# inputsheild_3.net
KiCad netlist of a schematic drawn in EAGLE
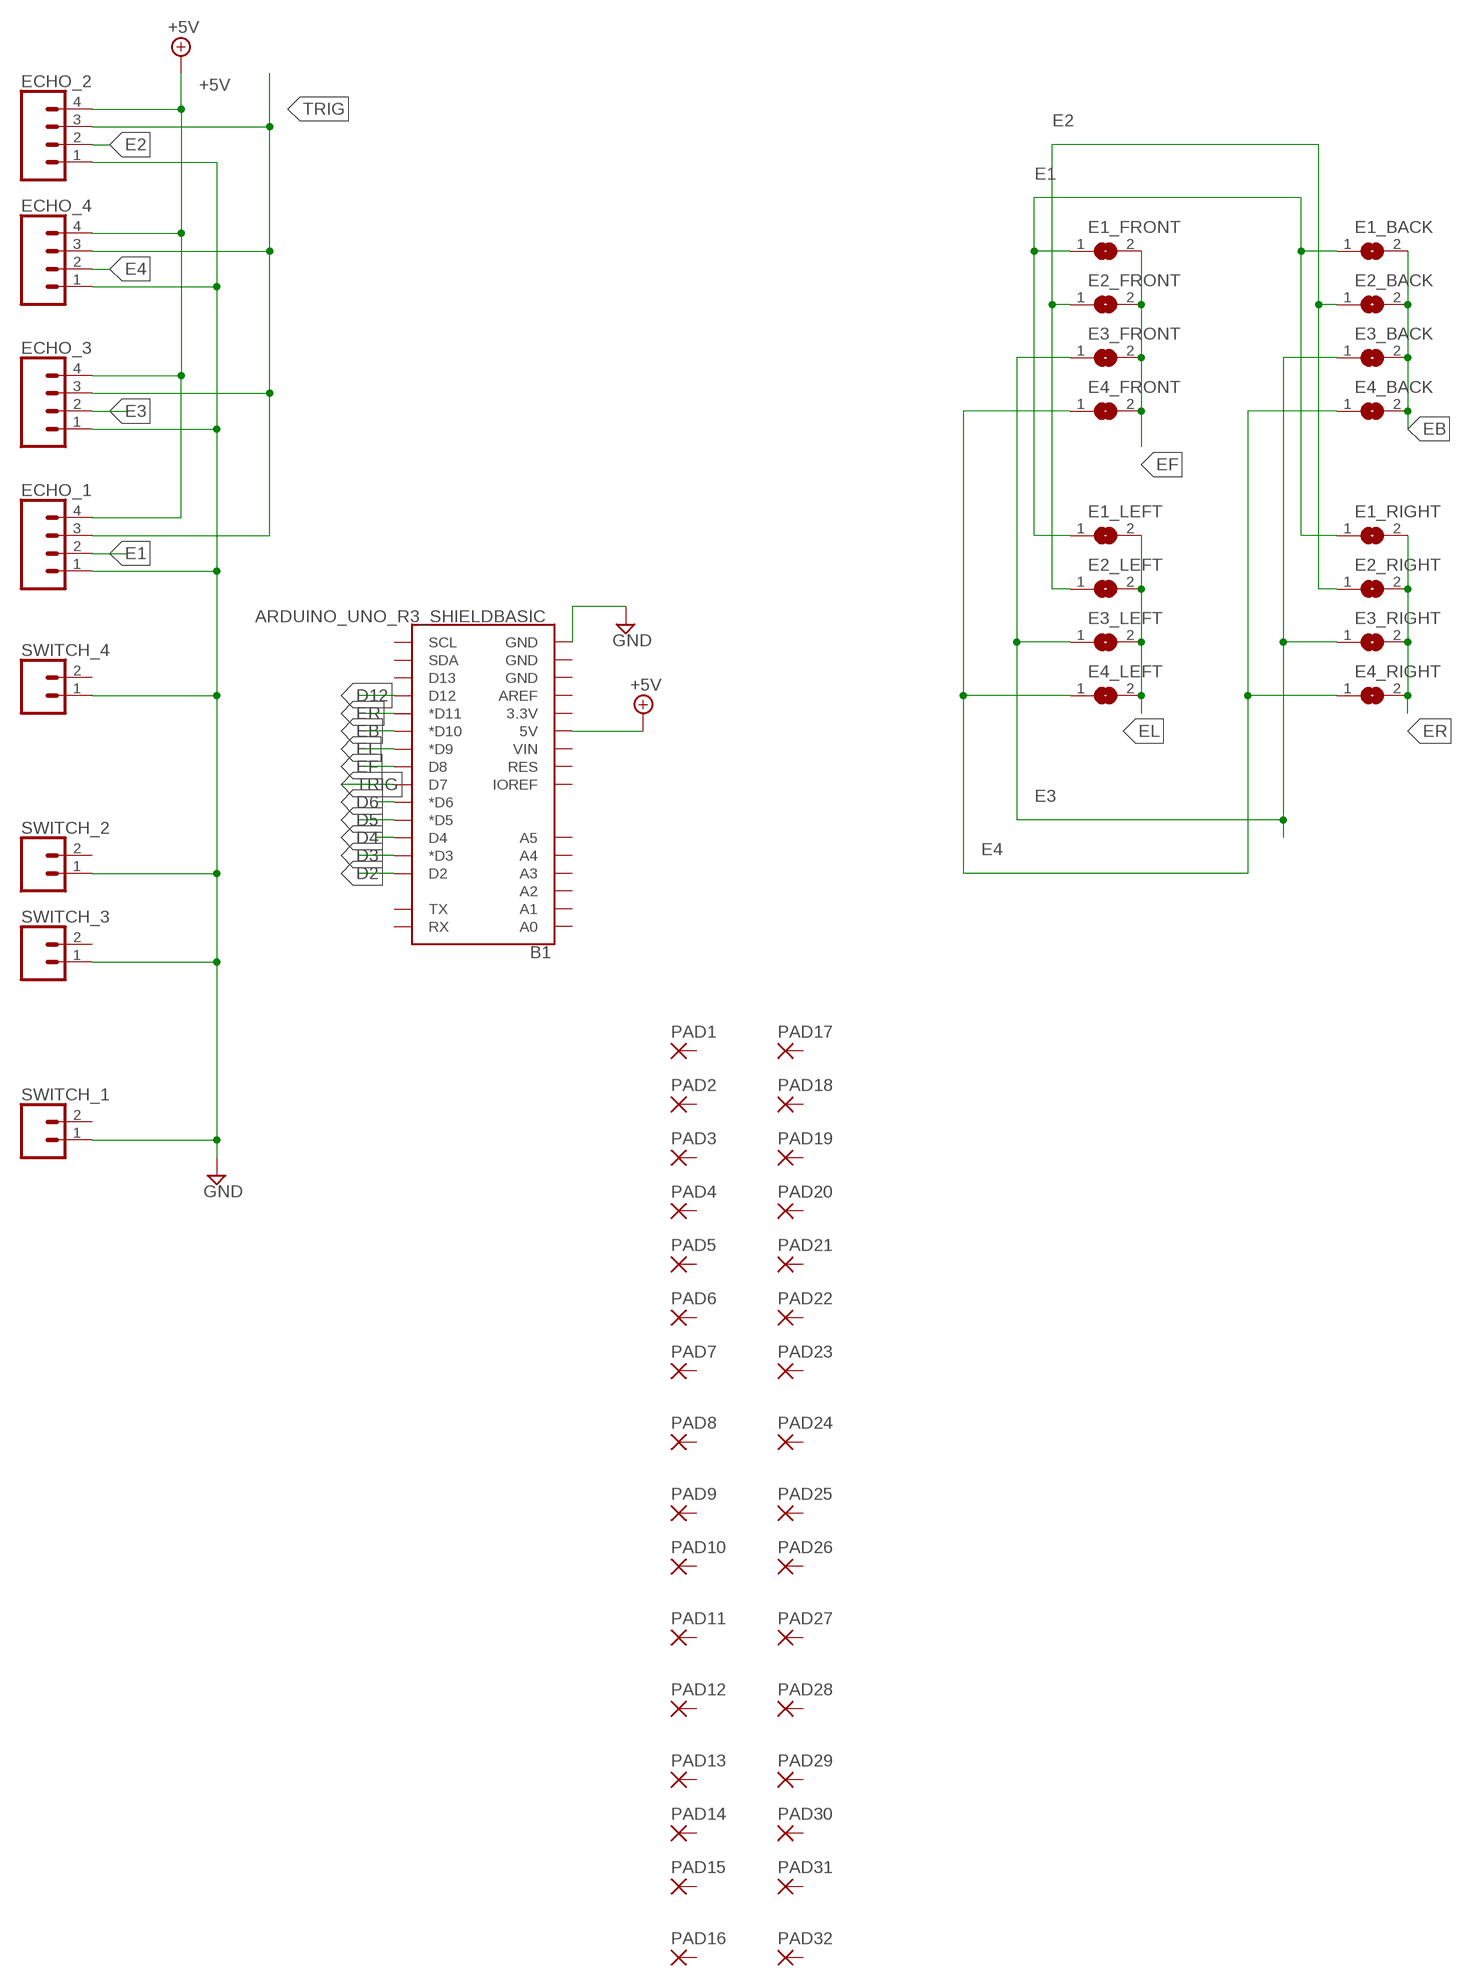
[diagram p0: schematic, sheet 1]

(export (version "E")
  (design (tool "Eeschema 10.0.6"))
  (components
    (comp (ref "B1")
      (value "ARDUINO_UNO_R3_SHIELDBASIC")
      (footprint "eagle-import:UNO_R3_SHIELD")
      (libsource (lib "eagle-import") (part "ARDUINO_UNO_R3_SHIELDBASIC"))
    )
    (comp (ref "E1_BACK")
      (value "SJ")
      (footprint "eagle-import:SJ")
      (libsource (lib "eagle-import") (part "SJ"))
    )
    (comp (ref "E1_FRONT")
      (value "SJ")
      (footprint "eagle-import:SJ")
      (libsource (lib "eagle-import") (part "SJ"))
    )
    (comp (ref "E1_LEFT")
      (value "SJ")
      (footprint "eagle-import:SJ")
      (libsource (lib "eagle-import") (part "SJ"))
    )
    (comp (ref "E1_RIGHT")
      (value "SJ")
      (footprint "eagle-import:SJ")
      (libsource (lib "eagle-import") (part "SJ"))
    )
    (comp (ref "E2_BACK")
      (value "SJ")
      (footprint "eagle-import:SJ")
      (libsource (lib "eagle-import") (part "SJ"))
    )
    (comp (ref "E2_FRONT")
      (value "SJ")
      (footprint "eagle-import:SJ")
      (libsource (lib "eagle-import") (part "SJ"))
    )
    (comp (ref "E2_LEFT")
      (value "SJ")
      (footprint "eagle-import:SJ")
      (libsource (lib "eagle-import") (part "SJ"))
    )
    (comp (ref "E2_RIGHT")
      (value "SJ")
      (footprint "eagle-import:SJ")
      (libsource (lib "eagle-import") (part "SJ"))
    )
    (comp (ref "E3_BACK")
      (value "SJ")
      (footprint "eagle-import:SJ")
      (libsource (lib "eagle-import") (part "SJ"))
    )
    (comp (ref "E3_FRONT")
      (value "SJ")
      (footprint "eagle-import:SJ")
      (libsource (lib "eagle-import") (part "SJ"))
    )
    (comp (ref "E3_LEFT")
      (value "SJ")
      (footprint "eagle-import:SJ")
      (libsource (lib "eagle-import") (part "SJ"))
    )
    (comp (ref "E3_RIGHT")
      (value "SJ")
      (footprint "eagle-import:SJ")
      (libsource (lib "eagle-import") (part "SJ"))
    )
    (comp (ref "E4_BACK")
      (value "SJ")
      (footprint "eagle-import:SJ")
      (libsource (lib "eagle-import") (part "SJ"))
    )
    (comp (ref "E4_FRONT")
      (value "SJ")
      (footprint "eagle-import:SJ")
      (libsource (lib "eagle-import") (part "SJ"))
    )
    (comp (ref "E4_LEFT")
      (value "SJ")
      (footprint "eagle-import:SJ")
      (libsource (lib "eagle-import") (part "SJ"))
    )
    (comp (ref "E4_RIGHT")
      (value "SJ")
      (footprint "eagle-import:SJ")
      (libsource (lib "eagle-import") (part "SJ"))
    )
    (comp (ref "ECHO_1")
      (value "CONN_04SCREW")
      (footprint "eagle-import:SCREWTERMINAL-3.5MM-4")
      (libsource (lib "eagle-import") (part "CONN_04SCREW"))
    )
    (comp (ref "ECHO_2")
      (value "CONN_04SCREW")
      (footprint "eagle-import:SCREWTERMINAL-3.5MM-4")
      (libsource (lib "eagle-import") (part "CONN_04SCREW"))
    )
    (comp (ref "ECHO_3")
      (value "CONN_04SCREW")
      (footprint "eagle-import:SCREWTERMINAL-3.5MM-4")
      (libsource (lib "eagle-import") (part "CONN_04SCREW"))
    )
    (comp (ref "ECHO_4")
      (value "CONN_04SCREW")
      (footprint "eagle-import:SCREWTERMINAL-3.5MM-4")
      (libsource (lib "eagle-import") (part "CONN_04SCREW"))
    )
    (comp (ref "PAD1")
      (value "SMD5")
      (footprint "eagle-import:SMD2,54-5,08")
      (libsource (lib "eagle-import") (part "SMD5"))
    )
    (comp (ref "PAD2")
      (value "SMD5")
      (footprint "eagle-import:SMD2,54-5,08")
      (libsource (lib "eagle-import") (part "SMD5"))
    )
    (comp (ref "PAD3")
      (value "SMD5")
      (footprint "eagle-import:SMD2,54-5,08")
      (libsource (lib "eagle-import") (part "SMD5"))
    )
    (comp (ref "PAD4")
      (value "SMD5")
      (footprint "eagle-import:SMD2,54-5,08")
      (libsource (lib "eagle-import") (part "SMD5"))
    )
    (comp (ref "PAD5")
      (value "SMD5")
      (footprint "eagle-import:SMD2,54-5,08")
      (libsource (lib "eagle-import") (part "SMD5"))
    )
    (comp (ref "PAD6")
      (value "SMD5")
      (footprint "eagle-import:SMD2,54-5,08")
      (libsource (lib "eagle-import") (part "SMD5"))
    )
    (comp (ref "PAD7")
      (value "SMD5")
      (footprint "eagle-import:SMD2,54-5,08")
      (libsource (lib "eagle-import") (part "SMD5"))
    )
    (comp (ref "PAD8")
      (value "SMD5")
      (footprint "eagle-import:SMD2,54-5,08")
      (libsource (lib "eagle-import") (part "SMD5"))
    )
    (comp (ref "PAD9")
      (value "SMD5")
      (footprint "eagle-import:SMD2,54-5,08")
      (libsource (lib "eagle-import") (part "SMD5"))
    )
    (comp (ref "PAD10")
      (value "SMD5")
      (footprint "eagle-import:SMD2,54-5,08")
      (libsource (lib "eagle-import") (part "SMD5"))
    )
    (comp (ref "PAD11")
      (value "SMD5")
      (footprint "eagle-import:SMD2,54-5,08")
      (libsource (lib "eagle-import") (part "SMD5"))
    )
    (comp (ref "PAD12")
      (value "SMD5")
      (footprint "eagle-import:SMD2,54-5,08")
      (libsource (lib "eagle-import") (part "SMD5"))
    )
    (comp (ref "PAD13")
      (value "SMD5")
      (footprint "eagle-import:SMD2,54-5,08")
      (libsource (lib "eagle-import") (part "SMD5"))
    )
    (comp (ref "PAD14")
      (value "SMD5")
      (footprint "eagle-import:SMD2,54-5,08")
      (libsource (lib "eagle-import") (part "SMD5"))
    )
    (comp (ref "PAD15")
      (value "SMD5")
      (footprint "eagle-import:SMD2,54-5,08")
      (libsource (lib "eagle-import") (part "SMD5"))
    )
    (comp (ref "PAD16")
      (value "SMD5")
      (footprint "eagle-import:SMD2,54-5,08")
      (libsource (lib "eagle-import") (part "SMD5"))
    )
    (comp (ref "PAD17")
      (value "SMD5")
      (footprint "eagle-import:SMD2,54-5,08")
      (libsource (lib "eagle-import") (part "SMD5"))
    )
    (comp (ref "PAD18")
      (value "SMD5")
      (footprint "eagle-import:SMD2,54-5,08")
      (libsource (lib "eagle-import") (part "SMD5"))
    )
    (comp (ref "PAD19")
      (value "SMD5")
      (footprint "eagle-import:SMD2,54-5,08")
      (libsource (lib "eagle-import") (part "SMD5"))
    )
    (comp (ref "PAD20")
      (value "SMD5")
      (footprint "eagle-import:SMD2,54-5,08")
      (libsource (lib "eagle-import") (part "SMD5"))
    )
    (comp (ref "PAD21")
      (value "SMD5")
      (footprint "eagle-import:SMD2,54-5,08")
      (libsource (lib "eagle-import") (part "SMD5"))
    )
    (comp (ref "PAD22")
      (value "SMD5")
      (footprint "eagle-import:SMD2,54-5,08")
      (libsource (lib "eagle-import") (part "SMD5"))
    )
    (comp (ref "PAD23")
      (value "SMD5")
      (footprint "eagle-import:SMD2,54-5,08")
      (libsource (lib "eagle-import") (part "SMD5"))
    )
    (comp (ref "PAD24")
      (value "SMD5")
      (footprint "eagle-import:SMD2,54-5,08")
      (libsource (lib "eagle-import") (part "SMD5"))
    )
    (comp (ref "PAD25")
      (value "SMD5")
      (footprint "eagle-import:SMD2,54-5,08")
      (libsource (lib "eagle-import") (part "SMD5"))
    )
    (comp (ref "PAD26")
      (value "SMD5")
      (footprint "eagle-import:SMD2,54-5,08")
      (libsource (lib "eagle-import") (part "SMD5"))
    )
    (comp (ref "PAD27")
      (value "SMD5")
      (footprint "eagle-import:SMD2,54-5,08")
      (libsource (lib "eagle-import") (part "SMD5"))
    )
    (comp (ref "PAD28")
      (value "SMD5")
      (footprint "eagle-import:SMD2,54-5,08")
      (libsource (lib "eagle-import") (part "SMD5"))
    )
    (comp (ref "PAD29")
      (value "SMD5")
      (footprint "eagle-import:SMD2,54-5,08")
      (libsource (lib "eagle-import") (part "SMD5"))
    )
    (comp (ref "PAD30")
      (value "SMD5")
      (footprint "eagle-import:SMD2,54-5,08")
      (libsource (lib "eagle-import") (part "SMD5"))
    )
    (comp (ref "PAD31")
      (value "SMD5")
      (footprint "eagle-import:SMD2,54-5,08")
      (libsource (lib "eagle-import") (part "SMD5"))
    )
    (comp (ref "PAD32")
      (value "SMD5")
      (footprint "eagle-import:SMD2,54-5,08")
      (libsource (lib "eagle-import") (part "SMD5"))
    )
    (comp (ref "SWITCH_1")
      (value "CONN_023.5MM")
      (footprint "eagle-import:SCREWTERMINAL-3.5MM-2")
      (libsource (lib "eagle-import") (part "CONN_023.5MM"))
    )
    (comp (ref "SWITCH_2")
      (value "CONN_023.5MM")
      (footprint "eagle-import:SCREWTERMINAL-3.5MM-2")
      (libsource (lib "eagle-import") (part "CONN_023.5MM"))
    )
    (comp (ref "SWITCH_3")
      (value "CONN_023.5MM")
      (footprint "eagle-import:SCREWTERMINAL-3.5MM-2")
      (libsource (lib "eagle-import") (part "CONN_023.5MM"))
    )
    (comp (ref "SWITCH_4")
      (value "CONN_023.5MM")
      (footprint "eagle-import:SCREWTERMINAL-3.5MM-2")
      (libsource (lib "eagle-import") (part "CONN_023.5MM"))
    )
  )
  (nets
    (net (code "1") (name "+5V") (class "Default")
      (node (ref "B1") (pin "5V") (pinfunction "5V_5V") (pintype "bidirectional"))
      (node (ref "ECHO_1") (pin "4") (pinfunction "4_4") (pintype "passive"))
      (node (ref "ECHO_2") (pin "4") (pinfunction "4_4") (pintype "passive"))
      (node (ref "ECHO_3") (pin "4") (pinfunction "4_4") (pintype "passive"))
      (node (ref "ECHO_4") (pin "4") (pinfunction "4_4") (pintype "passive"))
    )
    (net (code "2") (name "D2") (class "Default")
      (node (ref "B1") (pin "D2") (pinfunction "D2_D2") (pintype "bidirectional"))
    )
    (net (code "3") (name "D3") (class "Default")
      (node (ref "B1") (pin "D3") (pinfunction "*D3_D3") (pintype "bidirectional"))
    )
    (net (code "4") (name "D4") (class "Default")
      (node (ref "B1") (pin "D4") (pinfunction "D4_D4") (pintype "bidirectional"))
    )
    (net (code "5") (name "D5") (class "Default")
      (node (ref "B1") (pin "D5") (pinfunction "*D5_D5") (pintype "bidirectional"))
    )
    (net (code "6") (name "D6") (class "Default")
      (node (ref "B1") (pin "D6") (pinfunction "*D6_D6") (pintype "bidirectional"))
    )
    (net (code "7") (name "D12") (class "Default")
      (node (ref "B1") (pin "D12") (pinfunction "D12_D12") (pintype "bidirectional"))
    )
    (net (code "8") (name "E1") (class "Default")
      (node (ref "E1_BACK") (pin "1") (pinfunction "1_1") (pintype "passive"))
      (node (ref "E1_FRONT") (pin "1") (pinfunction "1_1") (pintype "passive"))
      (node (ref "E1_LEFT") (pin "1") (pinfunction "1_1") (pintype "passive"))
      (node (ref "E1_RIGHT") (pin "1") (pinfunction "1_1") (pintype "passive"))
      (node (ref "ECHO_1") (pin "2") (pinfunction "2_2") (pintype "passive"))
    )
    (net (code "9") (name "E2") (class "Default")
      (node (ref "E2_BACK") (pin "1") (pinfunction "1_1") (pintype "passive"))
      (node (ref "E2_FRONT") (pin "1") (pinfunction "1_1") (pintype "passive"))
      (node (ref "E2_LEFT") (pin "1") (pinfunction "1_1") (pintype "passive"))
      (node (ref "E2_RIGHT") (pin "1") (pinfunction "1_1") (pintype "passive"))
      (node (ref "ECHO_2") (pin "2") (pinfunction "2_2") (pintype "passive"))
    )
    (net (code "10") (name "E3") (class "Default")
      (node (ref "E3_BACK") (pin "1") (pinfunction "1_1") (pintype "passive"))
      (node (ref "E3_FRONT") (pin "1") (pinfunction "1_1") (pintype "passive"))
      (node (ref "E3_LEFT") (pin "1") (pinfunction "1_1") (pintype "passive"))
      (node (ref "E3_RIGHT") (pin "1") (pinfunction "1_1") (pintype "passive"))
      (node (ref "ECHO_3") (pin "2") (pinfunction "2_2") (pintype "passive"))
    )
    (net (code "11") (name "E4") (class "Default")
      (node (ref "E4_BACK") (pin "1") (pinfunction "1_1") (pintype "passive"))
      (node (ref "E4_FRONT") (pin "1") (pinfunction "1_1") (pintype "passive"))
      (node (ref "E4_LEFT") (pin "1") (pinfunction "1_1") (pintype "passive"))
      (node (ref "E4_RIGHT") (pin "1") (pinfunction "1_1") (pintype "passive"))
      (node (ref "ECHO_4") (pin "2") (pinfunction "2_2") (pintype "passive"))
    )
    (net (code "12") (name "EB") (class "Default")
      (node (ref "B1") (pin "D10") (pinfunction "*D10_D10") (pintype "bidirectional"))
      (node (ref "E1_BACK") (pin "2") (pinfunction "2_2") (pintype "passive"))
      (node (ref "E2_BACK") (pin "2") (pinfunction "2_2") (pintype "passive"))
      (node (ref "E3_BACK") (pin "2") (pinfunction "2_2") (pintype "passive"))
      (node (ref "E4_BACK") (pin "2") (pinfunction "2_2") (pintype "passive"))
    )
    (net (code "13") (name "EF") (class "Default")
      (node (ref "B1") (pin "D8") (pinfunction "D8_D8") (pintype "bidirectional"))
      (node (ref "E1_FRONT") (pin "2") (pinfunction "2_2") (pintype "passive"))
      (node (ref "E2_FRONT") (pin "2") (pinfunction "2_2") (pintype "passive"))
      (node (ref "E3_FRONT") (pin "2") (pinfunction "2_2") (pintype "passive"))
      (node (ref "E4_FRONT") (pin "2") (pinfunction "2_2") (pintype "passive"))
    )
    (net (code "14") (name "EL") (class "Default")
      (node (ref "B1") (pin "D9") (pinfunction "*D9_D9") (pintype "bidirectional"))
      (node (ref "E1_LEFT") (pin "2") (pinfunction "2_2") (pintype "passive"))
      (node (ref "E2_LEFT") (pin "2") (pinfunction "2_2") (pintype "passive"))
      (node (ref "E3_LEFT") (pin "2") (pinfunction "2_2") (pintype "passive"))
      (node (ref "E4_LEFT") (pin "2") (pinfunction "2_2") (pintype "passive"))
    )
    (net (code "15") (name "ER") (class "Default")
      (node (ref "B1") (pin "D11") (pinfunction "*D11_D11") (pintype "bidirectional"))
      (node (ref "E1_RIGHT") (pin "2") (pinfunction "2_2") (pintype "passive"))
      (node (ref "E2_RIGHT") (pin "2") (pinfunction "2_2") (pintype "passive"))
      (node (ref "E3_RIGHT") (pin "2") (pinfunction "2_2") (pintype "passive"))
      (node (ref "E4_RIGHT") (pin "2") (pinfunction "2_2") (pintype "passive"))
    )
    (net (code "16") (name "GND") (class "Default")
      (node (ref "B1") (pin "GND@0") (pinfunction "GND_GND@0") (pintype "bidirectional"))
      (node (ref "ECHO_1") (pin "1") (pinfunction "1_1") (pintype "passive"))
      (node (ref "ECHO_2") (pin "1") (pinfunction "1_1") (pintype "passive"))
      (node (ref "ECHO_3") (pin "1") (pinfunction "1_1") (pintype "passive"))
      (node (ref "ECHO_4") (pin "1") (pinfunction "1_1") (pintype "passive"))
      (node (ref "SWITCH_1") (pin "1") (pinfunction "1_1") (pintype "passive"))
      (node (ref "SWITCH_2") (pin "1") (pinfunction "1_1") (pintype "passive"))
      (node (ref "SWITCH_3") (pin "1") (pinfunction "1_1") (pintype "passive"))
      (node (ref "SWITCH_4") (pin "1") (pinfunction "1_1") (pintype "passive"))
    )
    (net (code "17") (name "TRIG") (class "Default")
      (node (ref "B1") (pin "D7") (pinfunction "D7_D7") (pintype "bidirectional"))
      (node (ref "ECHO_1") (pin "3") (pinfunction "3_3") (pintype "passive"))
      (node (ref "ECHO_2") (pin "3") (pinfunction "3_3") (pintype "passive"))
      (node (ref "ECHO_3") (pin "3") (pinfunction "3_3") (pintype "passive"))
      (node (ref "ECHO_4") (pin "3") (pinfunction "3_3") (pintype "passive"))
    )
    (net (code "18") (name "unconnected-(B1-GND-PadGND@1)") (class "Default")
      (node (ref "B1") (pin "GND@1") (pinfunction "GND_GND@1") (pintype "bidirectional"))
    )
    (net (code "19") (name "unconnected-(B1-GND-PadGND@2)") (class "Default")
      (node (ref "B1") (pin "GND@2") (pinfunction "GND_GND@2") (pintype "bidirectional"))
    )
    (net (code "20") (name "unconnected-(B1-Pad3.3V)") (class "Default")
      (node (ref "B1") (pin "3.3V") (pinfunction "3.3V_3.3V") (pintype "bidirectional"))
    )
    (net (code "21") (name "unconnected-(B1-PadA0)") (class "Default")
      (node (ref "B1") (pin "A0") (pinfunction "A0_A0") (pintype "bidirectional"))
    )
    (net (code "22") (name "unconnected-(B1-PadA1)") (class "Default")
      (node (ref "B1") (pin "A1") (pinfunction "A1_A1") (pintype "bidirectional"))
    )
    (net (code "23") (name "unconnected-(B1-PadA2)") (class "Default")
      (node (ref "B1") (pin "A2") (pinfunction "A2_A2") (pintype "bidirectional"))
    )
    (net (code "24") (name "unconnected-(B1-PadA3)") (class "Default")
      (node (ref "B1") (pin "A3") (pinfunction "A3_A3") (pintype "bidirectional"))
    )
    (net (code "25") (name "unconnected-(B1-PadA4)") (class "Default")
      (node (ref "B1") (pin "A4") (pinfunction "A4_A4") (pintype "bidirectional"))
    )
    (net (code "26") (name "unconnected-(B1-PadA5)") (class "Default")
      (node (ref "B1") (pin "A5") (pinfunction "A5_A5") (pintype "bidirectional"))
    )
    (net (code "27") (name "unconnected-(B1-PadAREF)") (class "Default")
      (node (ref "B1") (pin "AREF") (pinfunction "AREF_AREF") (pintype "bidirectional"))
    )
    (net (code "28") (name "unconnected-(B1-PadD13)") (class "Default")
      (node (ref "B1") (pin "D13") (pinfunction "D13_D13") (pintype "bidirectional"))
    )
    (net (code "29") (name "unconnected-(B1-PadIOREF)") (class "Default")
      (node (ref "B1") (pin "IOREF") (pinfunction "IOREF_IOREF") (pintype "bidirectional"))
    )
    (net (code "30") (name "unconnected-(B1-PadRES)") (class "Default")
      (node (ref "B1") (pin "RES") (pinfunction "RES_RES") (pintype "bidirectional"))
    )
    (net (code "31") (name "unconnected-(B1-PadRX)") (class "Default")
      (node (ref "B1") (pin "RX") (pinfunction "RX_RX") (pintype "bidirectional"))
    )
    (net (code "32") (name "unconnected-(B1-PadSCL)") (class "Default")
      (node (ref "B1") (pin "SCL") (pinfunction "SCL_SCL") (pintype "bidirectional"))
    )
    (net (code "33") (name "unconnected-(B1-PadSDA)") (class "Default")
      (node (ref "B1") (pin "SDA") (pinfunction "SDA_SDA") (pintype "bidirectional"))
    )
    (net (code "34") (name "unconnected-(B1-PadTX)") (class "Default")
      (node (ref "B1") (pin "TX") (pinfunction "TX_TX") (pintype "bidirectional"))
    )
    (net (code "35") (name "unconnected-(B1-PadVIN)") (class "Default")
      (node (ref "B1") (pin "VIN") (pinfunction "VIN_VIN") (pintype "bidirectional"))
    )
    (net (code "36") (name "unconnected-(PAD1-P-Pad1)") (class "Default")
      (node (ref "PAD1") (pin "1") (pinfunction "P_1") (pintype "passive"))
    )
    (net (code "37") (name "unconnected-(PAD2-P-Pad1)") (class "Default")
      (node (ref "PAD2") (pin "1") (pinfunction "P_1") (pintype "passive"))
    )
    (net (code "38") (name "unconnected-(PAD3-P-Pad1)") (class "Default")
      (node (ref "PAD3") (pin "1") (pinfunction "P_1") (pintype "passive"))
    )
    (net (code "39") (name "unconnected-(PAD4-P-Pad1)") (class "Default")
      (node (ref "PAD4") (pin "1") (pinfunction "P_1") (pintype "passive"))
    )
    (net (code "40") (name "unconnected-(PAD5-P-Pad1)") (class "Default")
      (node (ref "PAD5") (pin "1") (pinfunction "P_1") (pintype "passive"))
    )
    (net (code "41") (name "unconnected-(PAD6-P-Pad1)") (class "Default")
      (node (ref "PAD6") (pin "1") (pinfunction "P_1") (pintype "passive"))
    )
    (net (code "42") (name "unconnected-(PAD7-P-Pad1)") (class "Default")
      (node (ref "PAD7") (pin "1") (pinfunction "P_1") (pintype "passive"))
    )
    (net (code "43") (name "unconnected-(PAD8-P-Pad1)") (class "Default")
      (node (ref "PAD8") (pin "1") (pinfunction "P_1") (pintype "passive"))
    )
    (net (code "44") (name "unconnected-(PAD9-P-Pad1)") (class "Default")
      (node (ref "PAD9") (pin "1") (pinfunction "P_1") (pintype "passive"))
    )
    (net (code "45") (name "unconnected-(PAD10-P-Pad1)") (class "Default")
      (node (ref "PAD10") (pin "1") (pinfunction "P_1") (pintype "passive"))
    )
    (net (code "46") (name "unconnected-(PAD11-P-Pad1)") (class "Default")
      (node (ref "PAD11") (pin "1") (pinfunction "P_1") (pintype "passive"))
    )
    (net (code "47") (name "unconnected-(PAD12-P-Pad1)") (class "Default")
      (node (ref "PAD12") (pin "1") (pinfunction "P_1") (pintype "passive"))
    )
    (net (code "48") (name "unconnected-(PAD13-P-Pad1)") (class "Default")
      (node (ref "PAD13") (pin "1") (pinfunction "P_1") (pintype "passive"))
    )
    (net (code "49") (name "unconnected-(PAD14-P-Pad1)") (class "Default")
      (node (ref "PAD14") (pin "1") (pinfunction "P_1") (pintype "passive"))
    )
    (net (code "50") (name "unconnected-(PAD15-P-Pad1)") (class "Default")
      (node (ref "PAD15") (pin "1") (pinfunction "P_1") (pintype "passive"))
    )
    (net (code "51") (name "unconnected-(PAD16-P-Pad1)") (class "Default")
      (node (ref "PAD16") (pin "1") (pinfunction "P_1") (pintype "passive"))
    )
    (net (code "52") (name "unconnected-(PAD17-P-Pad1)") (class "Default")
      (node (ref "PAD17") (pin "1") (pinfunction "P_1") (pintype "passive"))
    )
    (net (code "53") (name "unconnected-(PAD18-P-Pad1)") (class "Default")
      (node (ref "PAD18") (pin "1") (pinfunction "P_1") (pintype "passive"))
    )
    (net (code "54") (name "unconnected-(PAD19-P-Pad1)") (class "Default")
      (node (ref "PAD19") (pin "1") (pinfunction "P_1") (pintype "passive"))
    )
    (net (code "55") (name "unconnected-(PAD20-P-Pad1)") (class "Default")
      (node (ref "PAD20") (pin "1") (pinfunction "P_1") (pintype "passive"))
    )
    (net (code "56") (name "unconnected-(PAD21-P-Pad1)") (class "Default")
      (node (ref "PAD21") (pin "1") (pinfunction "P_1") (pintype "passive"))
    )
    (net (code "57") (name "unconnected-(PAD22-P-Pad1)") (class "Default")
      (node (ref "PAD22") (pin "1") (pinfunction "P_1") (pintype "passive"))
    )
    (net (code "58") (name "unconnected-(PAD23-P-Pad1)") (class "Default")
      (node (ref "PAD23") (pin "1") (pinfunction "P_1") (pintype "passive"))
    )
    (net (code "59") (name "unconnected-(PAD24-P-Pad1)") (class "Default")
      (node (ref "PAD24") (pin "1") (pinfunction "P_1") (pintype "passive"))
    )
    (net (code "60") (name "unconnected-(PAD25-P-Pad1)") (class "Default")
      (node (ref "PAD25") (pin "1") (pinfunction "P_1") (pintype "passive"))
    )
    (net (code "61") (name "unconnected-(PAD26-P-Pad1)") (class "Default")
      (node (ref "PAD26") (pin "1") (pinfunction "P_1") (pintype "passive"))
    )
    (net (code "62") (name "unconnected-(PAD27-P-Pad1)") (class "Default")
      (node (ref "PAD27") (pin "1") (pinfunction "P_1") (pintype "passive"))
    )
    (net (code "63") (name "unconnected-(PAD28-P-Pad1)") (class "Default")
      (node (ref "PAD28") (pin "1") (pinfunction "P_1") (pintype "passive"))
    )
    (net (code "64") (name "unconnected-(PAD29-P-Pad1)") (class "Default")
      (node (ref "PAD29") (pin "1") (pinfunction "P_1") (pintype "passive"))
    )
    (net (code "65") (name "unconnected-(PAD30-P-Pad1)") (class "Default")
      (node (ref "PAD30") (pin "1") (pinfunction "P_1") (pintype "passive"))
    )
    (net (code "66") (name "unconnected-(PAD31-P-Pad1)") (class "Default")
      (node (ref "PAD31") (pin "1") (pinfunction "P_1") (pintype "passive"))
    )
    (net (code "67") (name "unconnected-(PAD32-P-Pad1)") (class "Default")
      (node (ref "PAD32") (pin "1") (pinfunction "P_1") (pintype "passive"))
    )
    (net (code "68") (name "unconnected-(SWITCH_1-Pad2)") (class "Default")
      (node (ref "SWITCH_1") (pin "2") (pinfunction "2_2") (pintype "passive"))
    )
    (net (code "69") (name "unconnected-(SWITCH_2-Pad2)") (class "Default")
      (node (ref "SWITCH_2") (pin "2") (pinfunction "2_2") (pintype "passive"))
    )
    (net (code "70") (name "unconnected-(SWITCH_3-Pad2)") (class "Default")
      (node (ref "SWITCH_3") (pin "2") (pinfunction "2_2") (pintype "passive"))
    )
    (net (code "71") (name "unconnected-(SWITCH_4-Pad2)") (class "Default")
      (node (ref "SWITCH_4") (pin "2") (pinfunction "2_2") (pintype "passive"))
    )
  )
)
